# motorEncoder.net
KiCad netlist of a schematic drawn in Altium Designer
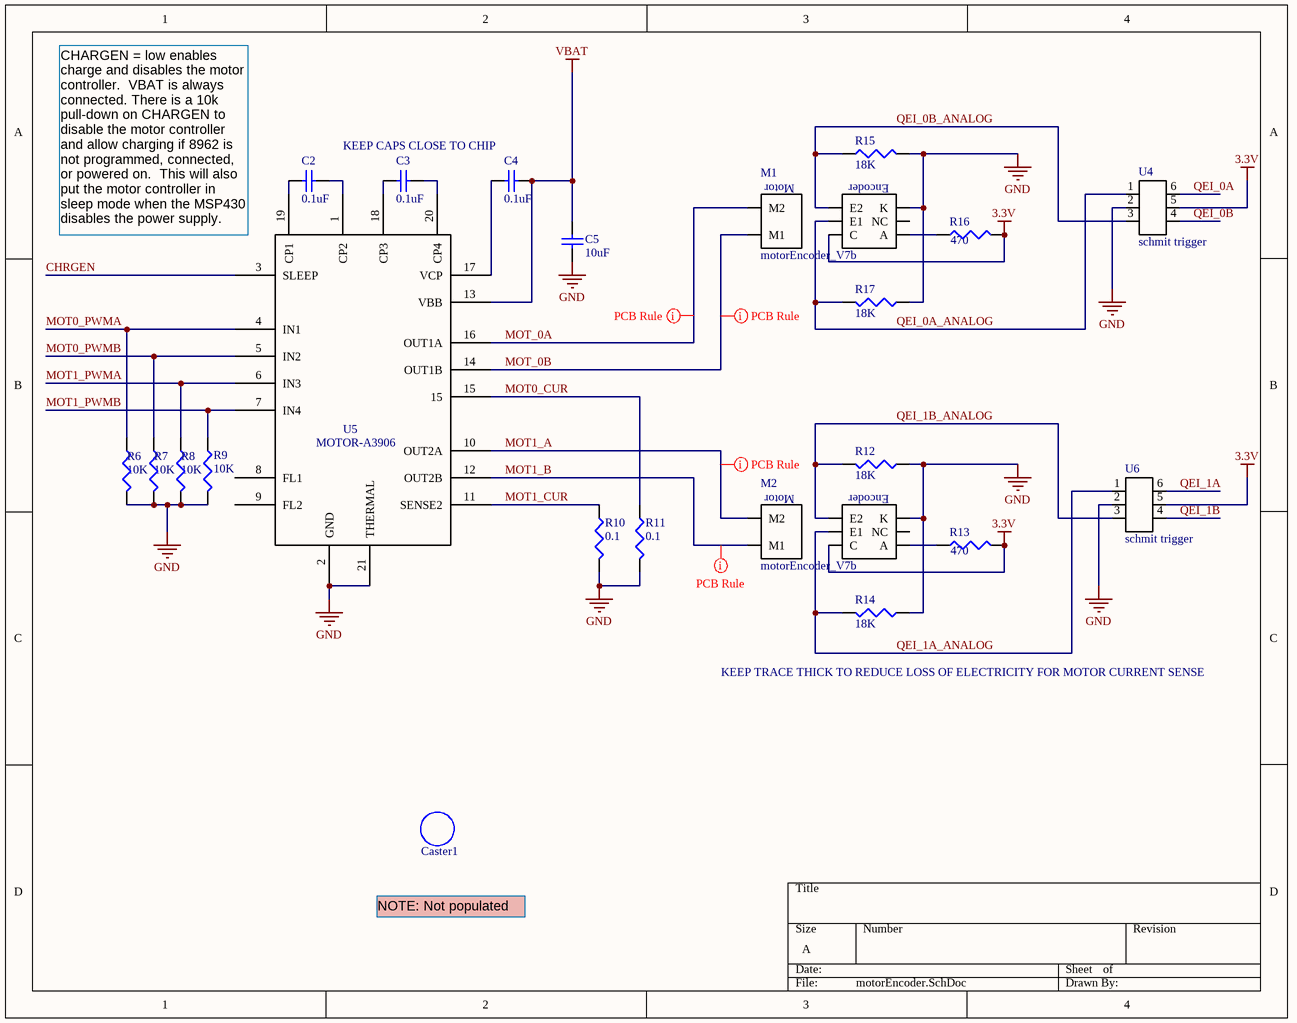
[diagram p0: motorEncoder.SchDoc]

(export (version "E")
  (design (tool "Eeschema 10.0.6"))
  (components
    (comp (ref "C2")
      (value "0.1uF")
      (footprint "CAPC1005L")
      (description "Capacitor (Semiconductor SIM Model)")
      (fields (field (name "Comment") "Cap Semi") (field (name "PUBLISHER") "Altium Limited"))
      (libsource (lib "Miscellaneous Devices") (part "Cap Semi"))
    )
    (comp (ref "C3")
      (value "0.1uF")
      (footprint "CAPC1005L")
      (description "Capacitor (Semiconductor SIM Model)")
      (fields (field (name "Comment") "Cap Semi") (field (name "PUBLISHER") "Altium Limited"))
      (libsource (lib "Miscellaneous Devices") (part "Cap Semi"))
    )
    (comp (ref "C4")
      (value "0.1uF")
      (footprint "CAPC1005L")
      (description "Capacitor (Semiconductor SIM Model)")
      (fields (field (name "Comment") "Cap Semi") (field (name "PUBLISHER") "Altium Limited"))
      (libsource (lib "Miscellaneous Devices") (part "Cap Semi"))
    )
    (comp (ref "C5")
      (value "10uF")
      (footprint "CAPC1608L")
      (description "Capacitor (Semiconductor SIM Model)")
      (fields (field (name "Comment") "Cap Semi") (field (name "PUBLISHER") "Altium Limited"))
      (libsource (lib "Miscellaneous Devices") (part "Cap Semi"))
    )
    (comp (ref "Caster1")
      (value "non connect")
      (footprint "3/4\"CASTER2")
      (description "This is just a space saver to get the caster onto the pcb")
      (libsource (lib "mrone") (part "Caster 3/4in"))
    )
    (comp (ref "M1")
      (value "motorEncoder_V7b")
      (footprint "motorEncoder_V7b")
      (libsource (lib "mrone") (part "motorEncoder_V7b"))
    )
    (comp (ref "M2")
      (value "motorEncoder_V7b")
      (footprint "motorEncoder_V7b")
      (libsource (lib "mrone") (part "motorEncoder_V7b"))
    )
    (comp (ref "R6")
      (value "10K")
      (footprint "RESC1608L")
      (description "Resistor")
      (fields (field (name "Comment") "Res3") (field (name "PUBLISHER") "Altium Limited"))
      (libsource (lib "Miscellaneous Devices") (part "Res3"))
    )
    (comp (ref "R7")
      (value "10K")
      (footprint "RESC1608L")
      (description "Resistor")
      (fields (field (name "Comment") "Res3") (field (name "PUBLISHER") "Altium Limited"))
      (libsource (lib "Miscellaneous Devices") (part "Res3"))
    )
    (comp (ref "R8")
      (value "10K")
      (footprint "RESC1608L")
      (description "Resistor")
      (fields (field (name "Comment") "Res3") (field (name "PUBLISHER") "Altium Limited"))
      (libsource (lib "Miscellaneous Devices") (part "Res3"))
    )
    (comp (ref "R9")
      (value "10K")
      (footprint "RESC1608L")
      (description "Resistor")
      (fields (field (name "Comment") "Res3") (field (name "PUBLISHER") "Altium Limited"))
      (libsource (lib "Miscellaneous Devices") (part "Res3"))
    )
    (comp (ref "R10")
      (value "0.1")
      (footprint "RESC1608L")
      (description "Resistor")
      (fields (field (name "Comment") "Res3") (field (name "PUBLISHER") "Altium Limited"))
      (libsource (lib "Miscellaneous Devices") (part "Res3"))
    )
    (comp (ref "R11")
      (value "0.1")
      (footprint "RESC1608L")
      (description "Resistor")
      (fields (field (name "Comment") "Res3") (field (name "PUBLISHER") "Altium Limited"))
      (libsource (lib "Miscellaneous Devices") (part "Res3"))
    )
    (comp (ref "R12")
      (value "18K")
      (footprint "RESC1608L")
      (description "Resistor")
      (fields (field (name "PUBLISHER") "Altium Limited"))
      (libsource (lib "Miscellaneous Devices") (part "Res3"))
    )
    (comp (ref "R13")
      (value "470")
      (footprint "RESC1608L")
      (description "Resistor")
      (fields (field (name "PUBLISHER") "Altium Limited"))
      (libsource (lib "Miscellaneous Devices") (part "Res3"))
    )
    (comp (ref "R14")
      (value "18K")
      (footprint "RESC1608L")
      (description "Resistor")
      (fields (field (name "PUBLISHER") "Altium Limited"))
      (libsource (lib "Miscellaneous Devices") (part "Res3"))
    )
    (comp (ref "R15")
      (value "18K")
      (footprint "RESC1608L")
      (description "Resistor")
      (fields (field (name "PUBLISHER") "Altium Limited"))
      (libsource (lib "Miscellaneous Devices") (part "Res3"))
    )
    (comp (ref "R16")
      (value "470")
      (footprint "RESC1608L")
      (description "Resistor")
      (fields (field (name "PUBLISHER") "Altium Limited"))
      (libsource (lib "Miscellaneous Devices") (part "Res3"))
    )
    (comp (ref "R17")
      (value "18K")
      (footprint "RESC1608L")
      (description "Resistor")
      (fields (field (name "PUBLISHER") "Altium Limited"))
      (libsource (lib "Miscellaneous Devices") (part "Res3"))
    )
    (comp (ref "U4")
      (value "schmit trigger")
      (footprint "DCK(R-PDSO-C6)")
      (libsource (lib "mrone") (part "schmit trigger"))
    )
    (comp (ref "U5")
      (value "MOTOR-A3906")
      (footprint "QFN-20")
      (libsource (lib "V2_altium") (part "MOTOR-A3906"))
    )
    (comp (ref "U6")
      (value "schmit trigger")
      (footprint "DCK(R-PDSO-C6)")
      (libsource (lib "mrone") (part "schmit trigger"))
    )
  )
  (nets
    (net (code "2") (name "/CHRGEN") (class "Default")
      (node (ref "U5") (pin "3") (pinfunction "SLEEP_3") (pintype "passive"))
    )
    (net (code "3") (name "/MOT0_CUR") (class "Default")
      (node (ref "R11") (pin "1") (pinfunction "1_1") (pintype "passive"))
      (node (ref "U5") (pin "15") (pinfunction "15_15") (pintype "passive"))
    )
    (net (code "4") (name "/MOT0_PWMA") (class "Default")
      (node (ref "R6") (pin "1") (pinfunction "1_1") (pintype "passive"))
      (node (ref "U5") (pin "4") (pinfunction "IN1_4") (pintype "passive"))
    )
    (net (code "5") (name "/MOT0_PWMB") (class "Default")
      (node (ref "R7") (pin "1") (pinfunction "1_1") (pintype "passive"))
      (node (ref "U5") (pin "5") (pinfunction "IN2_5") (pintype "passive"))
    )
    (net (code "6") (name "/MOT1_A") (class "Default")
      (node (ref "M2") (pin "M2") (pinfunction "M2_M2") (pintype "passive"))
      (node (ref "U5") (pin "10") (pinfunction "OUT2A_10") (pintype "passive"))
    )
    (net (code "7") (name "/MOT1_B") (class "Default")
      (node (ref "M2") (pin "M1") (pinfunction "M1_M1") (pintype "passive"))
      (node (ref "U5") (pin "12") (pinfunction "OUT2B_12") (pintype "passive"))
    )
    (net (code "8") (name "/MOT1_CUR") (class "Default")
      (node (ref "R10") (pin "1") (pinfunction "1_1") (pintype "passive"))
      (node (ref "U5") (pin "11") (pinfunction "SENSE2_11") (pintype "passive"))
    )
    (net (code "9") (name "/MOT1_PWMA") (class "Default")
      (node (ref "R8") (pin "1") (pinfunction "1_1") (pintype "passive"))
      (node (ref "U5") (pin "6") (pinfunction "IN3_6") (pintype "passive"))
    )
    (net (code "10") (name "/MOT1_PWMB") (class "Default")
      (node (ref "R9") (pin "1") (pinfunction "1_1") (pintype "passive"))
      (node (ref "U5") (pin "7") (pinfunction "IN4_7") (pintype "passive"))
    )
    (net (code "11") (name "/MOT_0A") (class "Default")
      (node (ref "M1") (pin "M2") (pinfunction "M2_M2") (pintype "passive"))
      (node (ref "U5") (pin "16") (pinfunction "OUT1A_16") (pintype "passive"))
    )
    (net (code "12") (name "/MOT_0B") (class "Default")
      (node (ref "M1") (pin "M1") (pinfunction "M1_M1") (pintype "passive"))
      (node (ref "U5") (pin "14") (pinfunction "OUT1B_14") (pintype "passive"))
    )
    (net (code "13") (name "/QEI_0A") (class "Default")
      (node (ref "U4") (pin "6") (pinfunction "4_6") (pintype "passive"))
    )
    (net (code "14") (name "/QEI_0A_ANALOG") (class "Default")
      (node (ref "M1") (pin "E1") (pinfunction "E1_E1") (pintype "passive"))
      (node (ref "R17") (pin "2") (pinfunction "2_2") (pintype "passive"))
      (node (ref "U4") (pin "1") (pinfunction "1_1") (pintype "passive"))
    )
    (net (code "15") (name "/QEI_0B") (class "Default")
      (node (ref "U4") (pin "4") (pinfunction "4_4") (pintype "passive"))
    )
    (net (code "16") (name "/QEI_0B_ANALOG") (class "Default")
      (node (ref "M1") (pin "E2") (pinfunction "E2_E2") (pintype "passive"))
      (node (ref "R15") (pin "1") (pinfunction "1_1") (pintype "passive"))
      (node (ref "U4") (pin "3") (pinfunction "3_3") (pintype "passive"))
    )
    (net (code "17") (name "/QEI_1A") (class "Default")
      (node (ref "U6") (pin "6") (pinfunction "4_6") (pintype "passive"))
    )
    (net (code "18") (name "/QEI_1A_ANALOG") (class "Default")
      (node (ref "M2") (pin "E1") (pinfunction "E1_E1") (pintype "passive"))
      (node (ref "R14") (pin "2") (pinfunction "2_2") (pintype "passive"))
      (node (ref "U6") (pin "1") (pinfunction "1_1") (pintype "passive"))
    )
    (net (code "19") (name "/QEI_1B") (class "Default")
      (node (ref "U6") (pin "4") (pinfunction "4_4") (pintype "passive"))
    )
    (net (code "20") (name "/QEI_1B_ANALOG") (class "Default")
      (node (ref "M2") (pin "E2") (pinfunction "E2_E2") (pintype "passive"))
      (node (ref "R12") (pin "2") (pinfunction "2_2") (pintype "passive"))
      (node (ref "U6") (pin "3") (pinfunction "3_3") (pintype "passive"))
    )
    (net (code "21") (name "3.3V") (class "Default")
      (node (ref "M1") (pin "C") (pinfunction "C_C") (pintype "passive"))
      (node (ref "M2") (pin "C") (pinfunction "C_C") (pintype "passive"))
      (node (ref "R13") (pin "2") (pinfunction "2_2") (pintype "passive"))
      (node (ref "R16") (pin "2") (pinfunction "2_2") (pintype "passive"))
      (node (ref "U4") (pin "5") (pinfunction "5_5") (pintype "passive"))
      (node (ref "U6") (pin "5") (pinfunction "5_5") (pintype "passive"))
    )
    (net (code "22") (name "GND") (class "Default")
      (node (ref "C5") (pin "1") (pinfunction "1_1") (pintype "passive"))
      (node (ref "M1") (pin "K") (pinfunction "K_K") (pintype "passive"))
      (node (ref "M2") (pin "K") (pinfunction "K_K") (pintype "passive"))
      (node (ref "R10") (pin "2") (pinfunction "2_2") (pintype "passive"))
      (node (ref "R11") (pin "2") (pinfunction "2_2") (pintype "passive"))
      (node (ref "R12") (pin "1") (pinfunction "1_1") (pintype "passive"))
      (node (ref "R14") (pin "1") (pinfunction "1_1") (pintype "passive"))
      (node (ref "R15") (pin "2") (pinfunction "2_2") (pintype "passive"))
      (node (ref "R17") (pin "1") (pinfunction "1_1") (pintype "passive"))
      (node (ref "R6") (pin "2") (pinfunction "2_2") (pintype "passive"))
      (node (ref "R7") (pin "2") (pinfunction "2_2") (pintype "passive"))
      (node (ref "R8") (pin "2") (pinfunction "2_2") (pintype "passive"))
      (node (ref "R9") (pin "2") (pinfunction "2_2") (pintype "passive"))
      (node (ref "U4") (pin "2") (pinfunction "2_2") (pintype "passive"))
      (node (ref "U5") (pin "2") (pinfunction "GND_2") (pintype "passive"))
      (node (ref "U5") (pin "21") (pinfunction "THERMAL_21") (pintype "passive"))
      (node (ref "U6") (pin "2") (pinfunction "2_2") (pintype "passive"))
    )
    (net (code "23") (name "Net-(M1-PadA)") (class "Default")
      (node (ref "M1") (pin "A") (pinfunction "A_A") (pintype "passive"))
      (node (ref "R16") (pin "1") (pinfunction "1_1") (pintype "passive"))
    )
    (net (code "24") (name "Net-(M2-PadA)") (class "Default")
      (node (ref "M2") (pin "A") (pinfunction "A_A") (pintype "passive"))
      (node (ref "R13") (pin "1") (pinfunction "1_1") (pintype "passive"))
    )
    (net (code "25") (name "Net-(U5-CP1)") (class "Default")
      (node (ref "C2") (pin "1") (pinfunction "1_1") (pintype "passive"))
      (node (ref "U5") (pin "19") (pinfunction "CP1_19") (pintype "passive"))
    )
    (net (code "26") (name "Net-(U5-CP2)") (class "Default")
      (node (ref "C2") (pin "2") (pinfunction "2_2") (pintype "passive"))
      (node (ref "U5") (pin "1") (pinfunction "CP2_1") (pintype "passive"))
    )
    (net (code "27") (name "Net-(U5-CP3)") (class "Default")
      (node (ref "C3") (pin "1") (pinfunction "1_1") (pintype "passive"))
      (node (ref "U5") (pin "18") (pinfunction "CP3_18") (pintype "passive"))
    )
    (net (code "28") (name "Net-(U5-CP4)") (class "Default")
      (node (ref "C3") (pin "2") (pinfunction "2_2") (pintype "passive"))
      (node (ref "U5") (pin "20") (pinfunction "CP4_20") (pintype "passive"))
    )
    (net (code "29") (name "Net-(U5-VCP)") (class "Default")
      (node (ref "C4") (pin "2") (pinfunction "2_2") (pintype "passive"))
      (node (ref "U5") (pin "17") (pinfunction "VCP_17") (pintype "passive"))
    )
    (net (code "30") (name "VBAT") (class "Default")
      (node (ref "C4") (pin "1") (pinfunction "1_1") (pintype "passive"))
      (node (ref "C5") (pin "2") (pinfunction "2_2") (pintype "passive"))
      (node (ref "U5") (pin "13") (pinfunction "VBB_13") (pintype "passive"))
    )
    (net (code "31") (name "unconnected-(M1-PadNC)") (class "Default")
      (node (ref "M1") (pin "NC") (pinfunction "NC_NC") (pintype "passive"))
    )
    (net (code "32") (name "unconnected-(M2-PadNC)") (class "Default")
      (node (ref "M2") (pin "NC") (pinfunction "NC_NC") (pintype "passive"))
    )
    (net (code "33") (name "unconnected-(U5-FL1-Pad8)") (class "Default")
      (node (ref "U5") (pin "8") (pinfunction "FL1_8") (pintype "passive"))
    )
    (net (code "34") (name "unconnected-(U5-FL2-Pad9)") (class "Default")
      (node (ref "U5") (pin "9") (pinfunction "FL2_9") (pintype "passive"))
    )
  )
)
